# FAT35.net
KiCad netlist of a schematic drawn in Altium Designer
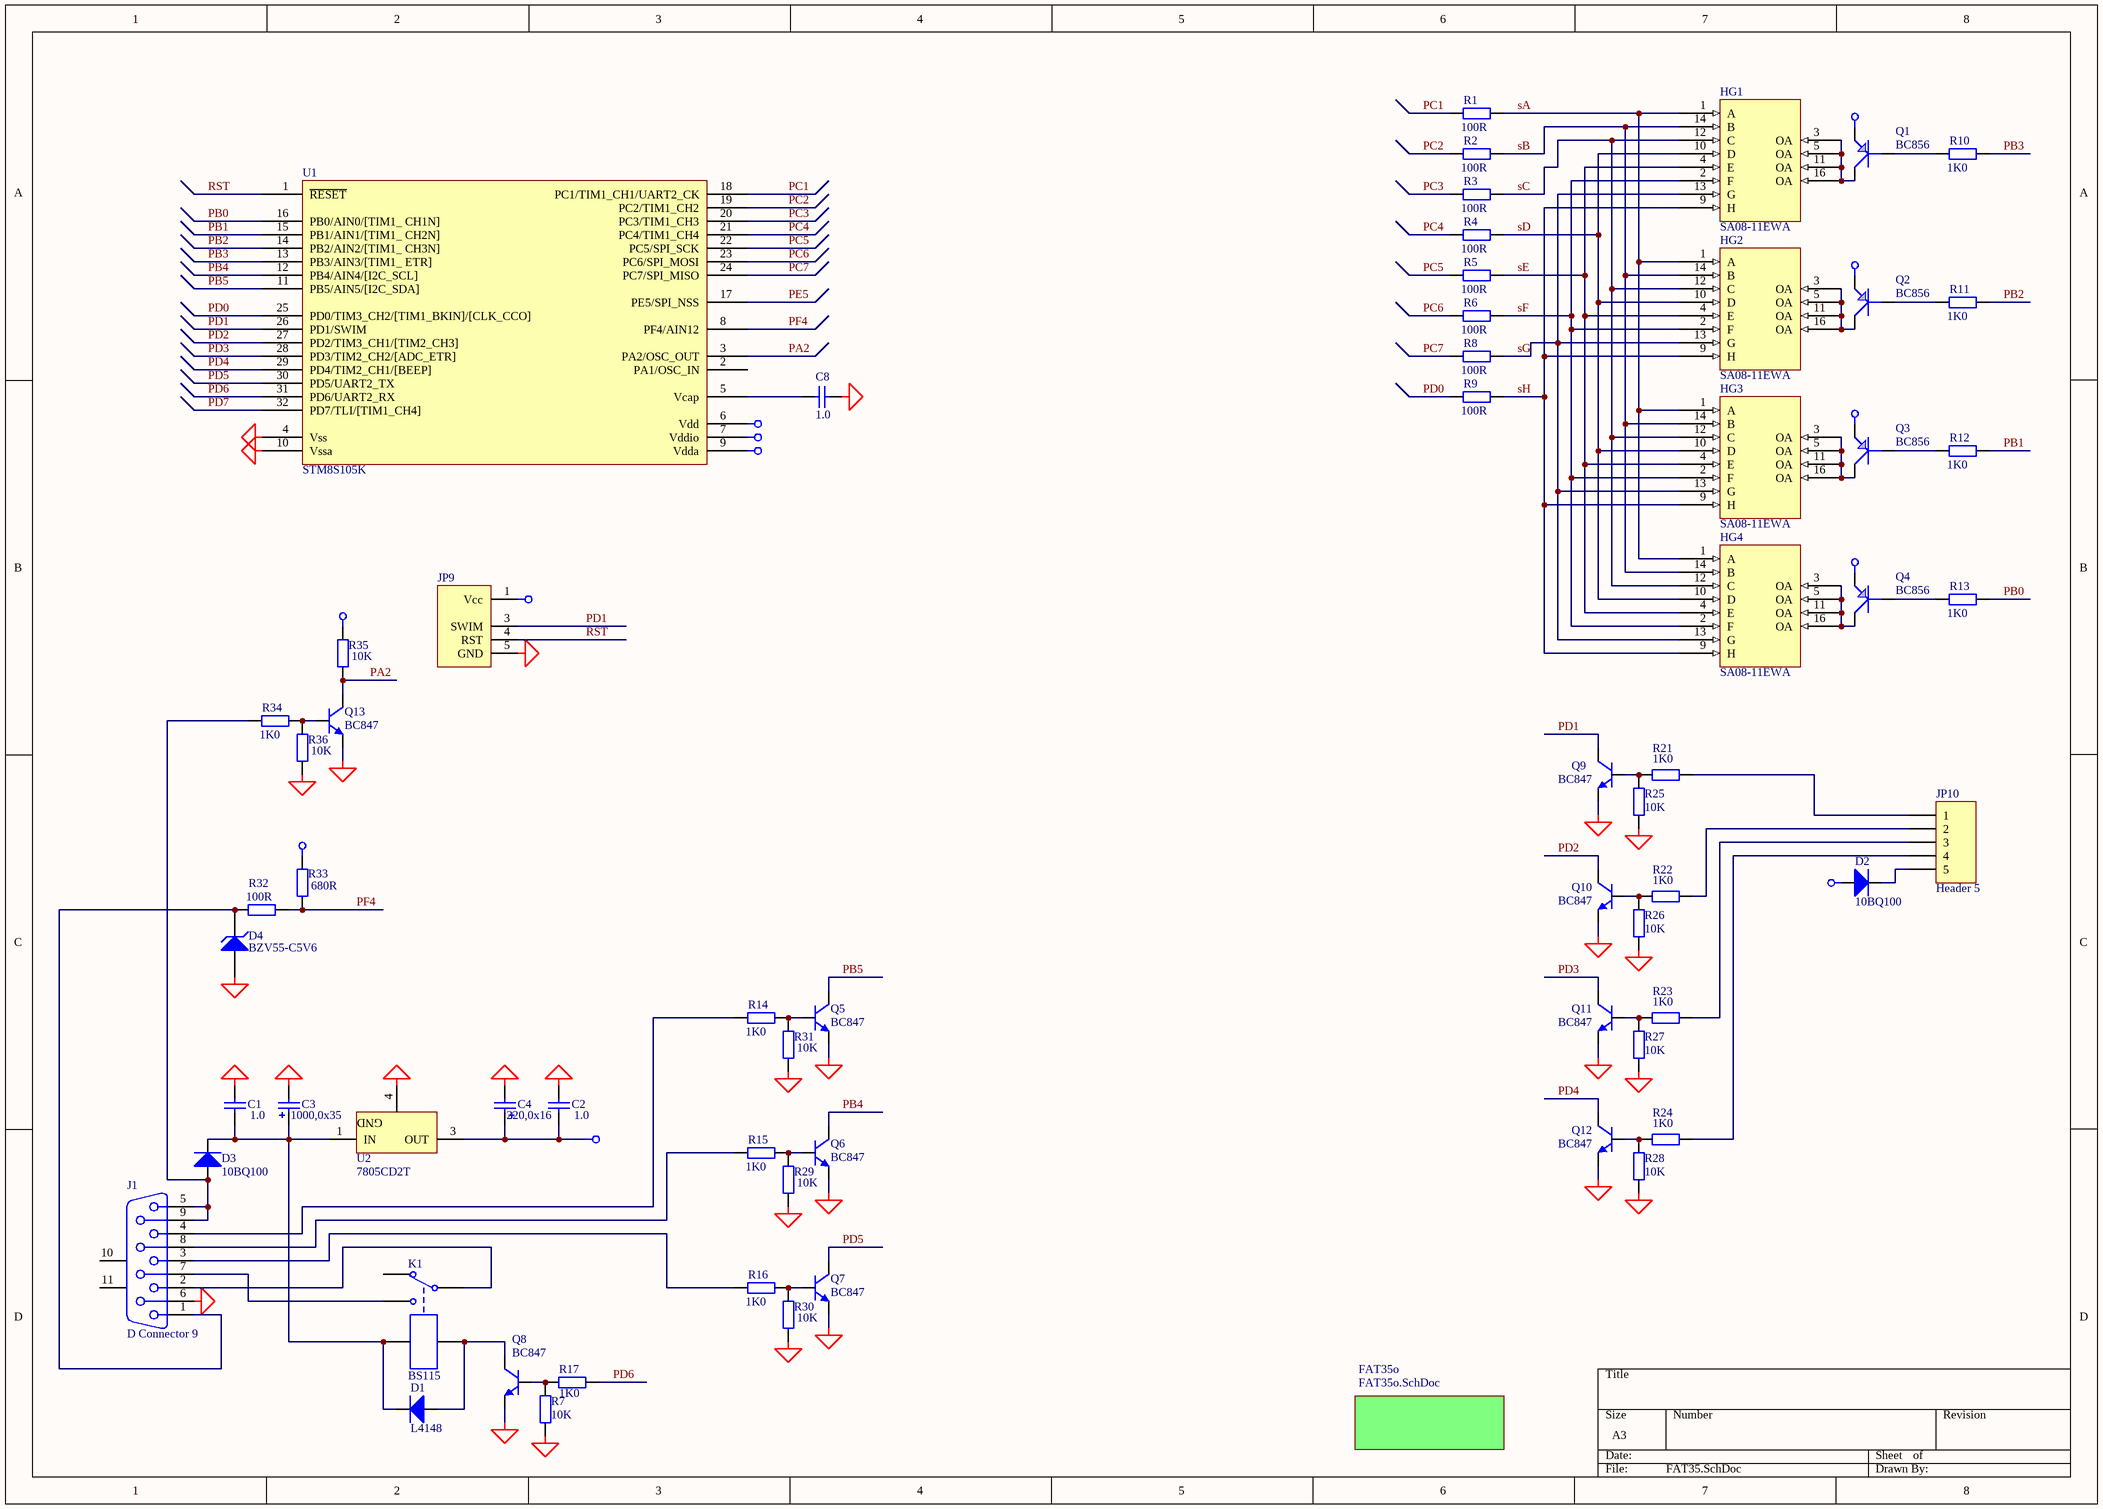
[diagram p0: FAT35.SchDoc]

(export (version "E")
  (design (tool "Eeschema 10.0.6"))
  (components
    (comp (ref "C1")
      (value "1.0")
      (footprint "_1206")
      (description "Capacitor (Semiconductor SIM Model)")
      (fields (field (name "MANUFACTURER") "Generic Components") (field (name "PUBLISHER") "Altium Limited"))
      (libsource (lib "Miscellaneous Devices") (part "Cap Semi"))
    )
    (comp (ref "C2")
      (value "1.0")
      (footprint "_1206")
      (description "Capacitor (Semiconductor SIM Model)")
      (fields (field (name "MANUFACTURER") "Generic Components") (field (name "PUBLISHER") "Altium Limited"))
      (libsource (lib "Miscellaneous Devices") (part "Cap Semi"))
    )
    (comp (ref "C3")
      (value "1000,0x35")
      (footprint "el3")
      (description "Polarized Capacitor (Radial)")
      (fields (field (name "MANUFACTURER") "Generic Components") (field (name "PUBLISHER") "Altium Limited"))
      (libsource (lib "PAL") (part "Cap Pol1"))
    )
    (comp (ref "C4")
      (value "220,0x16")
      (footprint "el3")
      (description "Polarized Capacitor (Radial)")
      (fields (field (name "MANUFACTURER") "Generic Components") (field (name "PUBLISHER") "Altium Limited"))
      (libsource (lib "PAL") (part "Cap Pol1"))
    )
    (comp (ref "C8")
      (value "1.0")
      (footprint "_1206")
      (description "Capacitor (Semiconductor SIM Model)")
      (fields (field (name "MANUFACTURER") "Generic Components") (field (name "PUBLISHER") "Altium Limited"))
      (libsource (lib "") (part "Cap Semi_1"))
    )
    (comp (ref "D1")
      (value "L4148")
      (footprint "_1206d")
      (description "Default Diode")
      (fields (field (name "MANUFACTURER") "Generic Components") (field (name "PUBLISHER") "Altium Limited"))
      (libsource (lib "PAL") (part "Diode"))
    )
    (comp (ref "D2")
      (value "10BQ100")
      (footprint "D_6_3")
      (description "Default Diode")
      (fields (field (name "MANUFACTURER") "Generic Components") (field (name "PUBLISHER") "Altium Limited"))
      (libsource (lib "PAL") (part "Diode"))
    )
    (comp (ref "D3")
      (value "10BQ100")
      (footprint "D_6_3")
      (description "Default Diode")
      (fields (field (name "MANUFACTURER") "Generic Components") (field (name "PUBLISHER") "Altium Limited"))
      (libsource (lib "") (part "Diode_1"))
    )
    (comp (ref "D4")
      (value "BZV55-C5V6")
      (footprint "_1206d")
      (description "Zener Diode")
      (fields (field (name "MANUFACTURER") "Generic Components") (field (name "PUBLISHER") "Altium Limited"))
      (libsource (lib "Miscellaneous Devices") (part "D Zener"))
    )
    (comp (ref "HG1") (value "SA08-11EWA") (footprint "SA08-11") (libsource (lib "PAL") (part "SA08-11EWA")))
    (comp (ref "HG2") (value "SA08-11EWA") (footprint "SA08-11") (libsource (lib "PAL") (part "SA08-11EWA")))
    (comp (ref "HG3") (value "SA08-11EWA") (footprint "SA08-11") (libsource (lib "PAL") (part "SA08-11EWA")))
    (comp (ref "HG4") (value "SA08-11EWA") (footprint "SA08-11") (libsource (lib "PAL") (part "SA08-11EWA")))
    (comp (ref "J1")
      (value "D Connector 9")
      (footprint "DSUB1.385-2H9")
      (description "Receptacle Assembly, 9 Position, Right Angle")
      (fields (field (name "MANUFACTURER") "Generic Components") (field (name "PUBLISHER") "Altium Limited"))
      (libsource (lib "Miscellaneous Connectors") (part "D Connector 9"))
    )
    (comp (ref "JP9") (value "~") (footprint "HDR1X5_uart") (libsource (lib "PAL") (part "SWIM_CONN")))
    (comp (ref "JP10")
      (value "Header 5")
      (footprint "HDR1X5")
      (description "Header, 5-Pin")
      (fields (field (name "MANUFACTURER") "Generic Components") (field (name "PUBLISHER") "Altium Limited"))
      (libsource (lib "Miscellaneous Connectors") (part "Header 5"))
    )
    (comp (ref "K1")
      (value "BS115")
      (footprint "BS115")
      (description "Single-Pole Dual-Throw Relay")
      (fields (field (name "MANUFACTURER") "Generic Components") (field (name "PUBLISHER") "Altium Limited"))
      (libsource (lib "PAL") (part "BS115"))
    )
    (comp (ref "Q1") (value "BC856") (footprint "SO-G3") (libsource (lib "MAIN") (part "GT109")))
    (comp (ref "Q2") (value "BC856") (footprint "SO-G3") (libsource (lib "MAIN") (part "GT109")))
    (comp (ref "Q3") (value "BC856") (footprint "SO-G3") (libsource (lib "MAIN") (part "GT109")))
    (comp (ref "Q4") (value "BC856") (footprint "SO-G3") (libsource (lib "MAIN") (part "GT109")))
    (comp (ref "Q5")
      (value "BC847")
      (footprint "SO-G3")
      (description "General Purpose Transistor NPN Silicon")
      (fields (field (name "MANUFACTURER") "Motorola") (field (name "PUBLISHER") "Altium Limited"))
      (libsource (lib "PAL") (part "BC847ALT1"))
    )
    (comp (ref "Q6")
      (value "BC847")
      (footprint "SO-G3")
      (description "General Purpose Transistor NPN Silicon")
      (fields (field (name "MANUFACTURER") "Motorola") (field (name "PUBLISHER") "Altium Limited"))
      (libsource (lib "PAL") (part "BC847ALT1"))
    )
    (comp (ref "Q7")
      (value "BC847")
      (footprint "SO-G3")
      (description "General Purpose Transistor NPN Silicon")
      (fields (field (name "MANUFACTURER") "Motorola") (field (name "PUBLISHER") "Altium Limited"))
      (libsource (lib "PAL") (part "BC847ALT1"))
    )
    (comp (ref "Q8")
      (value "BC847")
      (footprint "SO-G3")
      (description "General Purpose Transistor NPN Silicon")
      (fields (field (name "MANUFACTURER") "Motorola") (field (name "PUBLISHER") "Altium Limited"))
      (libsource (lib "PAL") (part "BC847ALT1"))
    )
    (comp (ref "Q9")
      (value "BC847")
      (footprint "SO-G3")
      (description "General Purpose Transistor NPN Silicon")
      (fields (field (name "MANUFACTURER") "Motorola") (field (name "PUBLISHER") "Altium Limited"))
      (libsource (lib "PAL") (part "BC847ALT1"))
    )
    (comp (ref "Q10")
      (value "BC847")
      (footprint "SO-G3")
      (description "General Purpose Transistor NPN Silicon")
      (fields (field (name "MANUFACTURER") "Motorola") (field (name "PUBLISHER") "Altium Limited"))
      (libsource (lib "PAL") (part "BC847ALT1"))
    )
    (comp (ref "Q11")
      (value "BC847")
      (footprint "SO-G3")
      (description "General Purpose Transistor NPN Silicon")
      (fields (field (name "MANUFACTURER") "Motorola") (field (name "PUBLISHER") "Altium Limited"))
      (libsource (lib "PAL") (part "BC847ALT1"))
    )
    (comp (ref "Q12")
      (value "BC847")
      (footprint "SO-G3")
      (description "General Purpose Transistor NPN Silicon")
      (fields (field (name "MANUFACTURER") "Motorola") (field (name "PUBLISHER") "Altium Limited"))
      (libsource (lib "PAL") (part "BC847ALT1"))
    )
    (comp (ref "Q13")
      (value "BC847")
      (footprint "SO-G3")
      (description "General Purpose Transistor NPN Silicon")
      (fields (field (name "MANUFACTURER") "Motorola") (field (name "PUBLISHER") "Altium Limited"))
      (libsource (lib "PAL") (part "BC847ALT1"))
    )
    (comp (ref "R1")
      (value "100R")
      (footprint "_1206")
      (description "Resistor")
      (fields (field (name "MANUFACTURER") "Generic Components") (field (name "PUBLISHER") "Altium Limited"))
      (libsource (lib "") (part "Res2_1"))
    )
    (comp (ref "R2")
      (value "100R")
      (footprint "_1206")
      (description "Resistor")
      (fields (field (name "MANUFACTURER") "Generic Components") (field (name "PUBLISHER") "Altium Limited"))
      (libsource (lib "") (part "Res2_1"))
    )
    (comp (ref "R3")
      (value "100R")
      (footprint "_1206")
      (description "Resistor")
      (fields (field (name "MANUFACTURER") "Generic Components") (field (name "PUBLISHER") "Altium Limited"))
      (libsource (lib "") (part "Res2_1"))
    )
    (comp (ref "R4")
      (value "100R")
      (footprint "_1206")
      (description "Resistor")
      (fields (field (name "MANUFACTURER") "Generic Components") (field (name "PUBLISHER") "Altium Limited"))
      (libsource (lib "") (part "Res2_1"))
    )
    (comp (ref "R5")
      (value "100R")
      (footprint "_1206")
      (description "Resistor")
      (fields (field (name "MANUFACTURER") "Generic Components") (field (name "PUBLISHER") "Altium Limited"))
      (libsource (lib "") (part "Res2_1"))
    )
    (comp (ref "R6")
      (value "100R")
      (footprint "_1206")
      (description "Resistor")
      (fields (field (name "MANUFACTURER") "Generic Components") (field (name "PUBLISHER") "Altium Limited"))
      (libsource (lib "") (part "Res2_1"))
    )
    (comp (ref "R7")
      (value "10K")
      (footprint "_1206")
      (description "Resistor")
      (fields (field (name "MANUFACTURER") "Generic Components") (field (name "PUBLISHER") "Altium Limited"))
      (libsource (lib "Miscellaneous Devices") (part "Res2"))
    )
    (comp (ref "R8")
      (value "100R")
      (footprint "_1206")
      (description "Resistor")
      (fields (field (name "MANUFACTURER") "Generic Components") (field (name "PUBLISHER") "Altium Limited"))
      (libsource (lib "") (part "Res2_1"))
    )
    (comp (ref "R9")
      (value "100R")
      (footprint "_1206")
      (description "Resistor")
      (fields (field (name "MANUFACTURER") "Generic Components") (field (name "PUBLISHER") "Altium Limited"))
      (libsource (lib "") (part "Res2_1"))
    )
    (comp (ref "R10")
      (value "1K0")
      (footprint "_1206")
      (description "Resistor")
      (fields (field (name "MANUFACTURER") "Generic Components") (field (name "PUBLISHER") "Altium Limited"))
      (libsource (lib "") (part "Res2_1"))
    )
    (comp (ref "R11")
      (value "1K0")
      (footprint "_1206")
      (description "Resistor")
      (fields (field (name "MANUFACTURER") "Generic Components") (field (name "PUBLISHER") "Altium Limited"))
      (libsource (lib "") (part "Res2_1"))
    )
    (comp (ref "R12")
      (value "1K0")
      (footprint "_1206")
      (description "Resistor")
      (fields (field (name "MANUFACTURER") "Generic Components") (field (name "PUBLISHER") "Altium Limited"))
      (libsource (lib "") (part "Res2_1"))
    )
    (comp (ref "R13")
      (value "1K0")
      (footprint "_1206")
      (description "Resistor")
      (fields (field (name "MANUFACTURER") "Generic Components") (field (name "PUBLISHER") "Altium Limited"))
      (libsource (lib "") (part "Res2_1"))
    )
    (comp (ref "R14")
      (value "1K0")
      (footprint "_1206")
      (description "Resistor")
      (fields (field (name "MANUFACTURER") "Generic Components") (field (name "PUBLISHER") "Altium Limited"))
      (libsource (lib "Miscellaneous Devices") (part "Res2"))
    )
    (comp (ref "R15")
      (value "1K0")
      (footprint "_1206")
      (description "Resistor")
      (fields (field (name "MANUFACTURER") "Generic Components") (field (name "PUBLISHER") "Altium Limited"))
      (libsource (lib "Miscellaneous Devices") (part "Res2"))
    )
    (comp (ref "R16")
      (value "1K0")
      (footprint "_1206")
      (description "Resistor")
      (fields (field (name "MANUFACTURER") "Generic Components") (field (name "PUBLISHER") "Altium Limited"))
      (libsource (lib "Miscellaneous Devices") (part "Res2"))
    )
    (comp (ref "R17")
      (value "1K0")
      (footprint "_1206")
      (description "Resistor")
      (fields (field (name "MANUFACTURER") "Generic Components") (field (name "PUBLISHER") "Altium Limited"))
      (libsource (lib "") (part "Res2_2"))
    )
    (comp (ref "R21")
      (value "1K0")
      (footprint "_1206")
      (description "Resistor")
      (fields (field (name "MANUFACTURER") "Generic Components") (field (name "PUBLISHER") "Altium Limited"))
      (libsource (lib "") (part "Res2_2"))
    )
    (comp (ref "R22")
      (value "1K0")
      (footprint "_1206")
      (description "Resistor")
      (fields (field (name "MANUFACTURER") "Generic Components") (field (name "PUBLISHER") "Altium Limited"))
      (libsource (lib "") (part "Res2_2"))
    )
    (comp (ref "R23")
      (value "1K0")
      (footprint "_1206")
      (description "Resistor")
      (fields (field (name "MANUFACTURER") "Generic Components") (field (name "PUBLISHER") "Altium Limited"))
      (libsource (lib "") (part "Res2_2"))
    )
    (comp (ref "R24")
      (value "1K0")
      (footprint "_1206")
      (description "Resistor")
      (fields (field (name "MANUFACTURER") "Generic Components") (field (name "PUBLISHER") "Altium Limited"))
      (libsource (lib "") (part "Res2_2"))
    )
    (comp (ref "R25")
      (value "10K")
      (footprint "_1206")
      (description "Resistor")
      (fields (field (name "MANUFACTURER") "Generic Components") (field (name "PUBLISHER") "Altium Limited"))
      (libsource (lib "Miscellaneous Devices") (part "Res2"))
    )
    (comp (ref "R26")
      (value "10K")
      (footprint "_1206")
      (description "Resistor")
      (fields (field (name "MANUFACTURER") "Generic Components") (field (name "PUBLISHER") "Altium Limited"))
      (libsource (lib "Miscellaneous Devices") (part "Res2"))
    )
    (comp (ref "R27")
      (value "10K")
      (footprint "_1206")
      (description "Resistor")
      (fields (field (name "MANUFACTURER") "Generic Components") (field (name "PUBLISHER") "Altium Limited"))
      (libsource (lib "Miscellaneous Devices") (part "Res2"))
    )
    (comp (ref "R28")
      (value "10K")
      (footprint "_1206")
      (description "Resistor")
      (fields (field (name "MANUFACTURER") "Generic Components") (field (name "PUBLISHER") "Altium Limited"))
      (libsource (lib "Miscellaneous Devices") (part "Res2"))
    )
    (comp (ref "R29")
      (value "10K")
      (footprint "_1206")
      (description "Resistor")
      (fields (field (name "MANUFACTURER") "Generic Components") (field (name "PUBLISHER") "Altium Limited"))
      (libsource (lib "") (part "Res2_3"))
    )
    (comp (ref "R30")
      (value "10K")
      (footprint "_1206")
      (description "Resistor")
      (fields (field (name "MANUFACTURER") "Generic Components") (field (name "PUBLISHER") "Altium Limited"))
      (libsource (lib "") (part "Res2_3"))
    )
    (comp (ref "R31")
      (value "10K")
      (footprint "_1206")
      (description "Resistor")
      (fields (field (name "MANUFACTURER") "Generic Components") (field (name "PUBLISHER") "Altium Limited"))
      (libsource (lib "") (part "Res2_3"))
    )
    (comp (ref "R32")
      (value "100R")
      (footprint "_1206")
      (description "Resistor")
      (fields (field (name "MANUFACTURER") "Generic Components") (field (name "PUBLISHER") "Altium Limited"))
      (libsource (lib "Miscellaneous Devices") (part "Res2"))
    )
    (comp (ref "R33")
      (value "680R")
      (footprint "_1206")
      (description "Resistor")
      (fields (field (name "MANUFACTURER") "Generic Components") (field (name "PUBLISHER") "Altium Limited"))
      (libsource (lib "") (part "Res2_4"))
    )
    (comp (ref "R34")
      (value "1K0")
      (footprint "_1206")
      (description "Resistor")
      (fields (field (name "MANUFACTURER") "Generic Components") (field (name "PUBLISHER") "Altium Limited"))
      (libsource (lib "Miscellaneous Devices") (part "Res2"))
    )
    (comp (ref "R35")
      (value "10K")
      (footprint "_1206")
      (description "Resistor")
      (fields (field (name "MANUFACTURER") "Generic Components") (field (name "PUBLISHER") "Altium Limited"))
      (libsource (lib "") (part "Res2_3"))
    )
    (comp (ref "R36")
      (value "10K")
      (footprint "_1206")
      (description "Resistor")
      (fields (field (name "MANUFACTURER") "Generic Components") (field (name "PUBLISHER") "Altium Limited"))
      (libsource (lib "") (part "Res2_3"))
    )
    (comp (ref "U1")
      (value "STM8S105K")
      (footprint "QFP7X7-G32/X.5N")
      (libsource (lib "PAL") (part "STM8S105K"))
    )
    (comp (ref "U2")
      (value "7805CD2T")
      (footprint "D2PAK")
      (description "Three-Terminal Medium Current Positive Voltage Regulator")
      (fields (field (name "MANUFACTURER") "ON Semiconductor") (field (name "PUBLISHER") "Altium Limited"))
      (libsource (lib "ON Semi Power Mgt Voltage Regulator") (part "MC78M05CDT"))
    )
  )
  (nets
    (net (code "1") (name "+5v") (class "Default")
      (node (ref "C2") (pin "2") (pinfunction "2_2") (pintype "passive"))
      (node (ref "C4") (pin "1") (pinfunction "1_1") (pintype "passive"))
      (node (ref "D2") (pin "1") (pinfunction "A_1") (pintype "passive"))
      (node (ref "JP9") (pin "1") (pinfunction "Vcc_1") (pintype "passive"))
      (node (ref "Q1") (pin "2") (pinfunction "E_2") (pintype "passive"))
      (node (ref "Q2") (pin "2") (pinfunction "E_2") (pintype "passive"))
      (node (ref "Q3") (pin "2") (pinfunction "E_2") (pintype "passive"))
      (node (ref "Q4") (pin "2") (pinfunction "E_2") (pintype "passive"))
      (node (ref "R33") (pin "1") (pinfunction "1_1") (pintype "passive"))
      (node (ref "R35") (pin "1") (pinfunction "1_1") (pintype "passive"))
      (node (ref "U1") (pin "6") (pinfunction "Vdd_6") (pintype "passive"))
      (node (ref "U1") (pin "7") (pinfunction "Vddio_7") (pintype "passive"))
      (node (ref "U1") (pin "9") (pinfunction "Vdda_9") (pintype "passive"))
      (node (ref "U2") (pin "3") (pinfunction "OUT_3") (pintype "power_in"))
    )
    (net (code "2") (name "/PA2") (class "Default")
      (node (ref "Q13") (pin "3") (pinfunction "C_3") (pintype "passive"))
      (node (ref "R35") (pin "2") (pinfunction "2_2") (pintype "passive"))
      (node (ref "U1") (pin "3") (pinfunction "PA2/OSC_OUT_3") (pintype "passive"))
    )
    (net (code "3") (name "/PB0") (class "Default")
      (node (ref "R13") (pin "1") (pinfunction "1_1") (pintype "passive"))
      (node (ref "U1") (pin "16") (pinfunction "PB0/AIN0/[TIM1__CH1N]_16") (pintype "passive"))
    )
    (net (code "4") (name "/PB1") (class "Default")
      (node (ref "R12") (pin "1") (pinfunction "1_1") (pintype "passive"))
      (node (ref "U1") (pin "15") (pinfunction "PB1/AIN1/[TIM1__CH2N]_15") (pintype "passive"))
    )
    (net (code "5") (name "/PB2") (class "Default")
      (node (ref "R11") (pin "1") (pinfunction "1_1") (pintype "passive"))
      (node (ref "U1") (pin "14") (pinfunction "PB2/AIN2/[TIM1__CH3N]_14") (pintype "passive"))
    )
    (net (code "6") (name "/PB3") (class "Default")
      (node (ref "R10") (pin "1") (pinfunction "1_1") (pintype "passive"))
      (node (ref "U1") (pin "13") (pinfunction "PB3/AIN3/[TIM1__ETR]_13") (pintype "passive"))
    )
    (net (code "7") (name "/PB4") (class "Default")
      (node (ref "Q6") (pin "3") (pinfunction "C_3") (pintype "passive"))
      (node (ref "U1") (pin "12") (pinfunction "PB4/AIN4/[I2C_SCL]_12") (pintype "passive"))
    )
    (net (code "8") (name "/PB5") (class "Default")
      (node (ref "Q5") (pin "3") (pinfunction "C_3") (pintype "passive"))
      (node (ref "U1") (pin "11") (pinfunction "PB5/AIN5/[I2C_SDA]_11") (pintype "passive"))
    )
    (net (code "9") (name "/PC1") (class "Default")
      (node (ref "R1") (pin "2") (pinfunction "2_2") (pintype "passive"))
      (node (ref "U1") (pin "18") (pinfunction "PC1/TIM1_CH1/UART2_CK_18") (pintype "passive"))
    )
    (net (code "10") (name "/PC2") (class "Default")
      (node (ref "R2") (pin "2") (pinfunction "2_2") (pintype "passive"))
      (node (ref "U1") (pin "19") (pinfunction "PC2/TIM1_CH2_19") (pintype "passive"))
    )
    (net (code "11") (name "/PC3") (class "Default")
      (node (ref "R3") (pin "2") (pinfunction "2_2") (pintype "passive"))
      (node (ref "U1") (pin "20") (pinfunction "PC3/TIM1_CH3_20") (pintype "passive"))
    )
    (net (code "12") (name "/PC4") (class "Default")
      (node (ref "R4") (pin "2") (pinfunction "2_2") (pintype "passive"))
      (node (ref "U1") (pin "21") (pinfunction "PC4/TIM1_CH4_21") (pintype "passive"))
    )
    (net (code "13") (name "/PC5") (class "Default")
      (node (ref "R5") (pin "2") (pinfunction "2_2") (pintype "passive"))
      (node (ref "U1") (pin "22") (pinfunction "PC5/SPI_SCK_22") (pintype "passive"))
    )
    (net (code "14") (name "/PC6") (class "Default")
      (node (ref "R6") (pin "2") (pinfunction "2_2") (pintype "passive"))
      (node (ref "U1") (pin "23") (pinfunction "PC6/SPI_MOSI_23") (pintype "passive"))
    )
    (net (code "15") (name "/PC7") (class "Default")
      (node (ref "R8") (pin "2") (pinfunction "2_2") (pintype "passive"))
      (node (ref "U1") (pin "24") (pinfunction "PC7/SPI_MISO_24") (pintype "passive"))
    )
    (net (code "16") (name "/PD0") (class "Default")
      (node (ref "R9") (pin "2") (pinfunction "2_2") (pintype "passive"))
      (node (ref "U1") (pin "25") (pinfunction "PD0/TIM3_CH2/[TIM1_BKIN]/[CLK_CCO]_25") (pintype "passive"))
    )
    (net (code "17") (name "/PD1") (class "Default")
      (node (ref "JP9") (pin "3") (pinfunction "SWIM_3") (pintype "passive"))
      (node (ref "Q9") (pin "3") (pinfunction "C_3") (pintype "passive"))
      (node (ref "U1") (pin "26") (pinfunction "PD1/SWIM_26") (pintype "passive"))
    )
    (net (code "18") (name "/PD2") (class "Default")
      (node (ref "Q10") (pin "3") (pinfunction "C_3") (pintype "passive"))
      (node (ref "U1") (pin "27") (pinfunction "PD2/TIM3_CH1/[TIM2_CH3]_27") (pintype "passive"))
    )
    (net (code "19") (name "/PD3") (class "Default")
      (node (ref "Q11") (pin "3") (pinfunction "C_3") (pintype "passive"))
      (node (ref "U1") (pin "28") (pinfunction "PD3/TIM2_CH2/[ADC_ETR]_28") (pintype "passive"))
    )
    (net (code "20") (name "/PD4") (class "Default")
      (node (ref "Q12") (pin "3") (pinfunction "C_3") (pintype "passive"))
      (node (ref "U1") (pin "29") (pinfunction "PD4/TIM2_CH1/[BEEP]_29") (pintype "passive"))
    )
    (net (code "21") (name "/PD5") (class "Default")
      (node (ref "Q7") (pin "3") (pinfunction "C_3") (pintype "passive"))
      (node (ref "U1") (pin "30") (pinfunction "PD5/UART2_TX_30") (pintype "passive"))
    )
    (net (code "22") (name "/PD6") (class "Default")
      (node (ref "R17") (pin "2") (pinfunction "2_2") (pintype "passive"))
      (node (ref "U1") (pin "31") (pinfunction "PD6/UART2_RX_31") (pintype "passive"))
    )
    (net (code "23") (name "/PD7") (class "Default")
      (node (ref "U1") (pin "32") (pinfunction "PD7/TLI/[TIM1_CH4]_32") (pintype "passive"))
    )
    (net (code "24") (name "/PE5") (class "Default")
      (node (ref "U1") (pin "17") (pinfunction "PE5/SPI_NSS_17") (pintype "passive"))
    )
    (net (code "25") (name "/PF4") (class "Default")
      (node (ref "R32") (pin "1") (pinfunction "1_1") (pintype "passive"))
      (node (ref "R33") (pin "2") (pinfunction "2_2") (pintype "passive"))
      (node (ref "U1") (pin "8") (pinfunction "PF4/AIN12_8") (pintype "passive"))
    )
    (net (code "26") (name "/RST") (class "Default")
      (node (ref "JP9") (pin "4") (pinfunction "RST_4") (pintype "passive"))
      (node (ref "U1") (pin "1") (pinfunction "~{RESET}_1") (pintype "passive"))
    )
    (net (code "27") (name "/sA") (class "Default")
      (node (ref "HG1") (pin "1") (pinfunction "A_1") (pintype "input"))
      (node (ref "HG2") (pin "1") (pinfunction "A_1") (pintype "input"))
      (node (ref "HG3") (pin "1") (pinfunction "A_1") (pintype "input"))
      (node (ref "HG4") (pin "1") (pinfunction "A_1") (pintype "input"))
      (node (ref "R1") (pin "1") (pinfunction "1_1") (pintype "passive"))
    )
    (net (code "28") (name "/sB") (class "Default")
      (node (ref "HG1") (pin "14") (pinfunction "B_14") (pintype "input"))
      (node (ref "HG2") (pin "14") (pinfunction "B_14") (pintype "input"))
      (node (ref "HG3") (pin "14") (pinfunction "B_14") (pintype "input"))
      (node (ref "HG4") (pin "14") (pinfunction "B_14") (pintype "input"))
      (node (ref "R2") (pin "1") (pinfunction "1_1") (pintype "passive"))
    )
    (net (code "29") (name "/sC") (class "Default")
      (node (ref "HG1") (pin "12") (pinfunction "C_12") (pintype "input"))
      (node (ref "HG2") (pin "12") (pinfunction "C_12") (pintype "input"))
      (node (ref "HG3") (pin "12") (pinfunction "C_12") (pintype "input"))
      (node (ref "HG4") (pin "12") (pinfunction "C_12") (pintype "input"))
      (node (ref "R3") (pin "1") (pinfunction "1_1") (pintype "passive"))
    )
    (net (code "30") (name "/sD") (class "Default")
      (node (ref "HG1") (pin "10") (pinfunction "D_10") (pintype "input"))
      (node (ref "HG2") (pin "10") (pinfunction "D_10") (pintype "input"))
      (node (ref "HG3") (pin "10") (pinfunction "D_10") (pintype "input"))
      (node (ref "HG4") (pin "10") (pinfunction "D_10") (pintype "input"))
      (node (ref "R4") (pin "1") (pinfunction "1_1") (pintype "passive"))
    )
    (net (code "31") (name "/sE") (class "Default")
      (node (ref "HG1") (pin "4") (pinfunction "E_4") (pintype "input"))
      (node (ref "HG2") (pin "4") (pinfunction "E_4") (pintype "input"))
      (node (ref "HG3") (pin "4") (pinfunction "E_4") (pintype "input"))
      (node (ref "HG4") (pin "4") (pinfunction "E_4") (pintype "input"))
      (node (ref "R5") (pin "1") (pinfunction "1_1") (pintype "passive"))
    )
    (net (code "32") (name "/sF") (class "Default")
      (node (ref "HG1") (pin "2") (pinfunction "F_2") (pintype "input"))
      (node (ref "HG2") (pin "2") (pinfunction "F_2") (pintype "input"))
      (node (ref "HG3") (pin "2") (pinfunction "F_2") (pintype "input"))
      (node (ref "HG4") (pin "2") (pinfunction "F_2") (pintype "input"))
      (node (ref "R6") (pin "1") (pinfunction "1_1") (pintype "passive"))
    )
    (net (code "33") (name "/sG") (class "Default")
      (node (ref "HG1") (pin "13") (pinfunction "G_13") (pintype "input"))
      (node (ref "HG2") (pin "13") (pinfunction "G_13") (pintype "input"))
      (node (ref "HG3") (pin "13") (pinfunction "G_13") (pintype "input"))
      (node (ref "HG4") (pin "13") (pinfunction "G_13") (pintype "input"))
      (node (ref "R8") (pin "1") (pinfunction "1_1") (pintype "passive"))
    )
    (net (code "34") (name "/sH") (class "Default")
      (node (ref "HG1") (pin "9") (pinfunction "H_9") (pintype "input"))
      (node (ref "HG2") (pin "9") (pinfunction "H_9") (pintype "input"))
      (node (ref "HG3") (pin "9") (pinfunction "H_9") (pintype "input"))
      (node (ref "HG4") (pin "9") (pinfunction "H_9") (pintype "input"))
      (node (ref "R9") (pin "1") (pinfunction "1_1") (pintype "passive"))
    )
    (net (code "35") (name "GND") (class "Default")
      (node (ref "C1") (pin "1") (pinfunction "1_1") (pintype "passive"))
      (node (ref "C2") (pin "1") (pinfunction "1_1") (pintype "passive"))
      (node (ref "C3") (pin "2") (pinfunction "2_2") (pintype "passive"))
      (node (ref "C4") (pin "2") (pinfunction "2_2") (pintype "passive"))
      (node (ref "C8") (pin "1") (pinfunction "1_1") (pintype "passive"))
      (node (ref "D4") (pin "1") (pinfunction "A_1") (pintype "passive"))
      (node (ref "J1") (pin "6") (pinfunction "6_6") (pintype "passive"))
      (node (ref "JP9") (pin "5") (pinfunction "GND_5") (pintype "passive"))
      (node (ref "Q10") (pin "2") (pinfunction "E_2") (pintype "passive"))
      (node (ref "Q11") (pin "2") (pinfunction "E_2") (pintype "passive"))
      (node (ref "Q12") (pin "2") (pinfunction "E_2") (pintype "passive"))
      (node (ref "Q13") (pin "2") (pinfunction "E_2") (pintype "passive"))
      (node (ref "Q5") (pin "2") (pinfunction "E_2") (pintype "passive"))
      (node (ref "Q6") (pin "2") (pinfunction "E_2") (pintype "passive"))
      (node (ref "Q7") (pin "2") (pinfunction "E_2") (pintype "passive"))
      (node (ref "Q8") (pin "2") (pinfunction "E_2") (pintype "passive"))
      (node (ref "Q9") (pin "2") (pinfunction "E_2") (pintype "passive"))
      (node (ref "R25") (pin "2") (pinfunction "2_2") (pintype "passive"))
      (node (ref "R26") (pin "2") (pinfunction "2_2") (pintype "passive"))
      (node (ref "R27") (pin "2") (pinfunction "2_2") (pintype "passive"))
      (node (ref "R28") (pin "2") (pinfunction "2_2") (pintype "passive"))
      (node (ref "R29") (pin "2") (pinfunction "2_2") (pintype "passive"))
      (node (ref "R30") (pin "2") (pinfunction "2_2") (pintype "passive"))
      (node (ref "R31") (pin "2") (pinfunction "2_2") (pintype "passive"))
      (node (ref "R36") (pin "2") (pinfunction "2_2") (pintype "passive"))
      (node (ref "R7") (pin "2") (pinfunction "2_2") (pintype "passive"))
      (node (ref "U1") (pin "10") (pinfunction "Vssa_10") (pintype "passive"))
      (node (ref "U1") (pin "4") (pinfunction "Vss_4") (pintype "passive"))
      (node (ref "U2") (pin "4") (pinfunction "GND_4") (pintype "power_in"))
    )
    (net (code "36") (name "Net-(D1-A)") (class "Default")
      (node (ref "D1") (pin "1") (pinfunction "A_1") (pintype "passive"))
      (node (ref "K1") (pin "4") (pinfunction "4_4") (pintype "passive"))
      (node (ref "Q8") (pin "3") (pinfunction "C_3") (pintype "passive"))
    )
    (net (code "37") (name "Net-(D1-K)") (class "Default")
      (node (ref "C1") (pin "2") (pinfunction "2_2") (pintype "passive"))
      (node (ref "C3") (pin "1") (pinfunction "1_1") (pintype "passive"))
      (node (ref "D1") (pin "2") (pinfunction "K_2") (pintype "passive"))
      (node (ref "D3") (pin "2") (pinfunction "K_2") (pintype "passive"))
      (node (ref "K1") (pin "5") (pinfunction "5_5") (pintype "passive"))
      (node (ref "U2") (pin "1") (pinfunction "IN_1") (pintype "power_in"))
    )
    (net (code "38") (name "Net-(D2-K)") (class "Default")
      (node (ref "D2") (pin "2") (pinfunction "K_2") (pintype "passive"))
      (node (ref "JP10") (pin "5") (pinfunction "5_5") (pintype "passive"))
    )
    (net (code "39") (name "Net-(D3-A)") (class "Default")
      (node (ref "D3") (pin "1") (pinfunction "A_1") (pintype "passive"))
      (node (ref "J1") (pin "5") (pinfunction "5_5") (pintype "passive"))
      (node (ref "J1") (pin "9") (pinfunction "9_9") (pintype "passive"))
      (node (ref "R34") (pin "2") (pinfunction "2_2") (pintype "passive"))
    )
    (net (code "40") (name "Net-(D4-K)") (class "Default")
      (node (ref "D4") (pin "2") (pinfunction "K_2") (pintype "passive"))
      (node (ref "J1") (pin "1") (pinfunction "1_1") (pintype "passive"))
      (node (ref "R32") (pin "2") (pinfunction "2_2") (pintype "passive"))
    )
    (net (code "41") (name "Net-(J1-Pad2)") (class "Default")
      (node (ref "J1") (pin "2") (pinfunction "2_2") (pintype "passive"))
      (node (ref "K1") (pin "1") (pinfunction "1_1") (pintype "passive"))
    )
    (net (code "42") (name "Net-(J1-Pad3)") (class "Default")
      (node (ref "J1") (pin "3") (pinfunction "3_3") (pintype "passive"))
      (node (ref "R16") (pin "2") (pinfunction "2_2") (pintype "passive"))
    )
    (net (code "43") (name "Net-(J1-Pad4)") (class "Default")
      (node (ref "J1") (pin "4") (pinfunction "4_4") (pintype "passive"))
      (node (ref "R14") (pin "2") (pinfunction "2_2") (pintype "passive"))
    )
    (net (code "44") (name "Net-(J1-Pad7)") (class "Default")
      (node (ref "J1") (pin "7") (pinfunction "7_7") (pintype "passive"))
      (node (ref "K1") (pin "3") (pinfunction "3_3") (pintype "passive"))
    )
    (net (code "45") (name "Net-(J1-Pad8)") (class "Default")
      (node (ref "J1") (pin "8") (pinfunction "8_8") (pintype "passive"))
      (node (ref "R15") (pin "2") (pinfunction "2_2") (pintype "passive"))
    )
    (net (code "46") (name "Net-(JP10-Pad1)") (class "Default")
      (node (ref "JP10") (pin "1") (pinfunction "1_1") (pintype "passive"))
      (node (ref "R21") (pin "2") (pinfunction "2_2") (pintype "passive"))
    )
    (net (code "47") (name "Net-(JP10-Pad2)") (class "Default")
      (node (ref "JP10") (pin "2") (pinfunction "2_2") (pintype "passive"))
      (node (ref "R22") (pin "2") (pinfunction "2_2") (pintype "passive"))
    )
    (net (code "48") (name "Net-(JP10-Pad3)") (class "Default")
      (node (ref "JP10") (pin "3") (pinfunction "3_3") (pintype "passive"))
      (node (ref "R23") (pin "2") (pinfunction "2_2") (pintype "passive"))
    )
    (net (code "49") (name "Net-(JP10-Pad4)") (class "Default")
      (node (ref "JP10") (pin "4") (pinfunction "4_4") (pintype "passive"))
      (node (ref "R24") (pin "2") (pinfunction "2_2") (pintype "passive"))
    )
    (net (code "50") (name "Net-(Q1-B)") (class "Default")
      (node (ref "Q1") (pin "1") (pinfunction "B_1") (pintype "passive"))
      (node (ref "R10") (pin "2") (pinfunction "2_2") (pintype "passive"))
    )
    (net (code "51") (name "Net-(Q1-C)") (class "Default")
      (node (ref "HG1") (pin "11") (pinfunction "OA_11") (pintype "input"))
      (node (ref "HG1") (pin "16") (pinfunction "OA_16") (pintype "input"))
      (node (ref "HG1") (pin "3") (pinfunction "OA_3") (pintype "input"))
      (node (ref "HG1") (pin "5") (pinfunction "OA_5") (pintype "input"))
      (node (ref "Q1") (pin "3") (pinfunction "C_3") (pintype "passive"))
    )
    (net (code "52") (name "Net-(Q2-B)") (class "Default")
      (node (ref "Q2") (pin "1") (pinfunction "B_1") (pintype "passive"))
      (node (ref "R11") (pin "2") (pinfunction "2_2") (pintype "passive"))
    )
    (net (code "53") (name "Net-(Q2-C)") (class "Default")
      (node (ref "HG2") (pin "11") (pinfunction "OA_11") (pintype "input"))
      (node (ref "HG2") (pin "16") (pinfunction "OA_16") (pintype "input"))
      (node (ref "HG2") (pin "3") (pinfunction "OA_3") (pintype "input"))
      (node (ref "HG2") (pin "5") (pinfunction "OA_5") (pintype "input"))
      (node (ref "Q2") (pin "3") (pinfunction "C_3") (pintype "passive"))
    )
    (net (code "54") (name "Net-(Q3-B)") (class "Default")
      (node (ref "Q3") (pin "1") (pinfunction "B_1") (pintype "passive"))
      (node (ref "R12") (pin "2") (pinfunction "2_2") (pintype "passive"))
    )
    (net (code "55") (name "Net-(Q3-C)") (class "Default")
      (node (ref "HG3") (pin "11") (pinfunction "OA_11") (pintype "input"))
      (node (ref "HG3") (pin "16") (pinfunction "OA_16") (pintype "input"))
      (node (ref "HG3") (pin "3") (pinfunction "OA_3") (pintype "input"))
      (node (ref "HG3") (pin "5") (pinfunction "OA_5") (pintype "input"))
      (node (ref "Q3") (pin "3") (pinfunction "C_3") (pintype "passive"))
    )
    (net (code "56") (name "Net-(Q4-B)") (class "Default")
      (node (ref "Q4") (pin "1") (pinfunction "B_1") (pintype "passive"))
      (node (ref "R13") (pin "2") (pinfunction "2_2") (pintype "passive"))
    )
    (net (code "57") (name "Net-(Q4-C)") (class "Default")
      (node (ref "HG4") (pin "11") (pinfunction "OA_11") (pintype "input"))
      (node (ref "HG4") (pin "16") (pinfunction "OA_16") (pintype "input"))
      (node (ref "HG4") (pin "3") (pinfunction "OA_3") (pintype "input"))
      (node (ref "HG4") (pin "5") (pinfunction "OA_5") (pintype "input"))
      (node (ref "Q4") (pin "3") (pinfunction "C_3") (pintype "passive"))
    )
    (net (code "58") (name "Net-(Q5-B)") (class "Default")
      (node (ref "Q5") (pin "1") (pinfunction "B_1") (pintype "passive"))
      (node (ref "R14") (pin "1") (pinfunction "1_1") (pintype "passive"))
      (node (ref "R31") (pin "1") (pinfunction "1_1") (pintype "passive"))
    )
    (net (code "59") (name "Net-(Q6-B)") (class "Default")
      (node (ref "Q6") (pin "1") (pinfunction "B_1") (pintype "passive"))
      (node (ref "R15") (pin "1") (pinfunction "1_1") (pintype "passive"))
      (node (ref "R29") (pin "1") (pinfunction "1_1") (pintype "passive"))
    )
    (net (code "60") (name "Net-(Q7-B)") (class "Default")
      (node (ref "Q7") (pin "1") (pinfunction "B_1") (pintype "passive"))
      (node (ref "R16") (pin "1") (pinfunction "1_1") (pintype "passive"))
      (node (ref "R30") (pin "1") (pinfunction "1_1") (pintype "passive"))
    )
    (net (code "61") (name "Net-(Q8-B)") (class "Default")
      (node (ref "Q8") (pin "1") (pinfunction "B_1") (pintype "passive"))
      (node (ref "R17") (pin "1") (pinfunction "1_1") (pintype "passive"))
      (node (ref "R7") (pin "1") (pinfunction "1_1") (pintype "passive"))
    )
    (net (code "62") (name "Net-(Q9-B)") (class "Default")
      (node (ref "Q9") (pin "1") (pinfunction "B_1") (pintype "passive"))
      (node (ref "R21") (pin "1") (pinfunction "1_1") (pintype "passive"))
      (node (ref "R25") (pin "1") (pinfunction "1_1") (pintype "passive"))
    )
    (net (code "63") (name "Net-(Q10-B)") (class "Default")
      (node (ref "Q10") (pin "1") (pinfunction "B_1") (pintype "passive"))
      (node (ref "R22") (pin "1") (pinfunction "1_1") (pintype "passive"))
      (node (ref "R26") (pin "1") (pinfunction "1_1") (pintype "passive"))
    )
    (net (code "64") (name "Net-(Q11-B)") (class "Default")
      (node (ref "Q11") (pin "1") (pinfunction "B_1") (pintype "passive"))
      (node (ref "R23") (pin "1") (pinfunction "1_1") (pintype "passive"))
      (node (ref "R27") (pin "1") (pinfunction "1_1") (pintype "passive"))
    )
    (net (code "65") (name "Net-(Q12-B)") (class "Default")
      (node (ref "Q12") (pin "1") (pinfunction "B_1") (pintype "passive"))
      (node (ref "R24") (pin "1") (pinfunction "1_1") (pintype "passive"))
      (node (ref "R28") (pin "1") (pinfunction "1_1") (pintype "passive"))
    )
    (net (code "66") (name "Net-(Q13-B)") (class "Default")
      (node (ref "Q13") (pin "1") (pinfunction "B_1") (pintype "passive"))
      (node (ref "R34") (pin "1") (pinfunction "1_1") (pintype "passive"))
      (node (ref "R36") (pin "1") (pinfunction "1_1") (pintype "passive"))
    )
    (net (code "67") (name "Net-(U1-Vcap)") (class "Default")
      (node (ref "C8") (pin "2") (pinfunction "2_2") (pintype "passive"))
      (node (ref "U1") (pin "5") (pinfunction "Vcap_5") (pintype "passive"))
    )
    (net (code "68") (name "unconnected-(J1-MH1-Pad10)") (class "Default")
      (node (ref "J1") (pin "10") (pinfunction "MH1_10") (pintype "passive"))
    )
    (net (code "69") (name "unconnected-(J1-MH2-Pad11)") (class "Default")
      (node (ref "J1") (pin "11") (pinfunction "MH2_11") (pintype "passive"))
    )
    (net (code "70") (name "unconnected-(K1-Pad2)") (class "Default")
      (node (ref "K1") (pin "2") (pinfunction "2_2") (pintype "passive"))
    )
    (net (code "71") (name "unconnected-(U1-PA1{slash}OSC_IN-Pad2)") (class "Default")
      (node (ref "U1") (pin "2") (pinfunction "PA1/OSC_IN_2") (pintype "passive"))
    )
  )
)
